# SmartLED1.net
KiCad netlist of a schematic drawn in Altium Designer
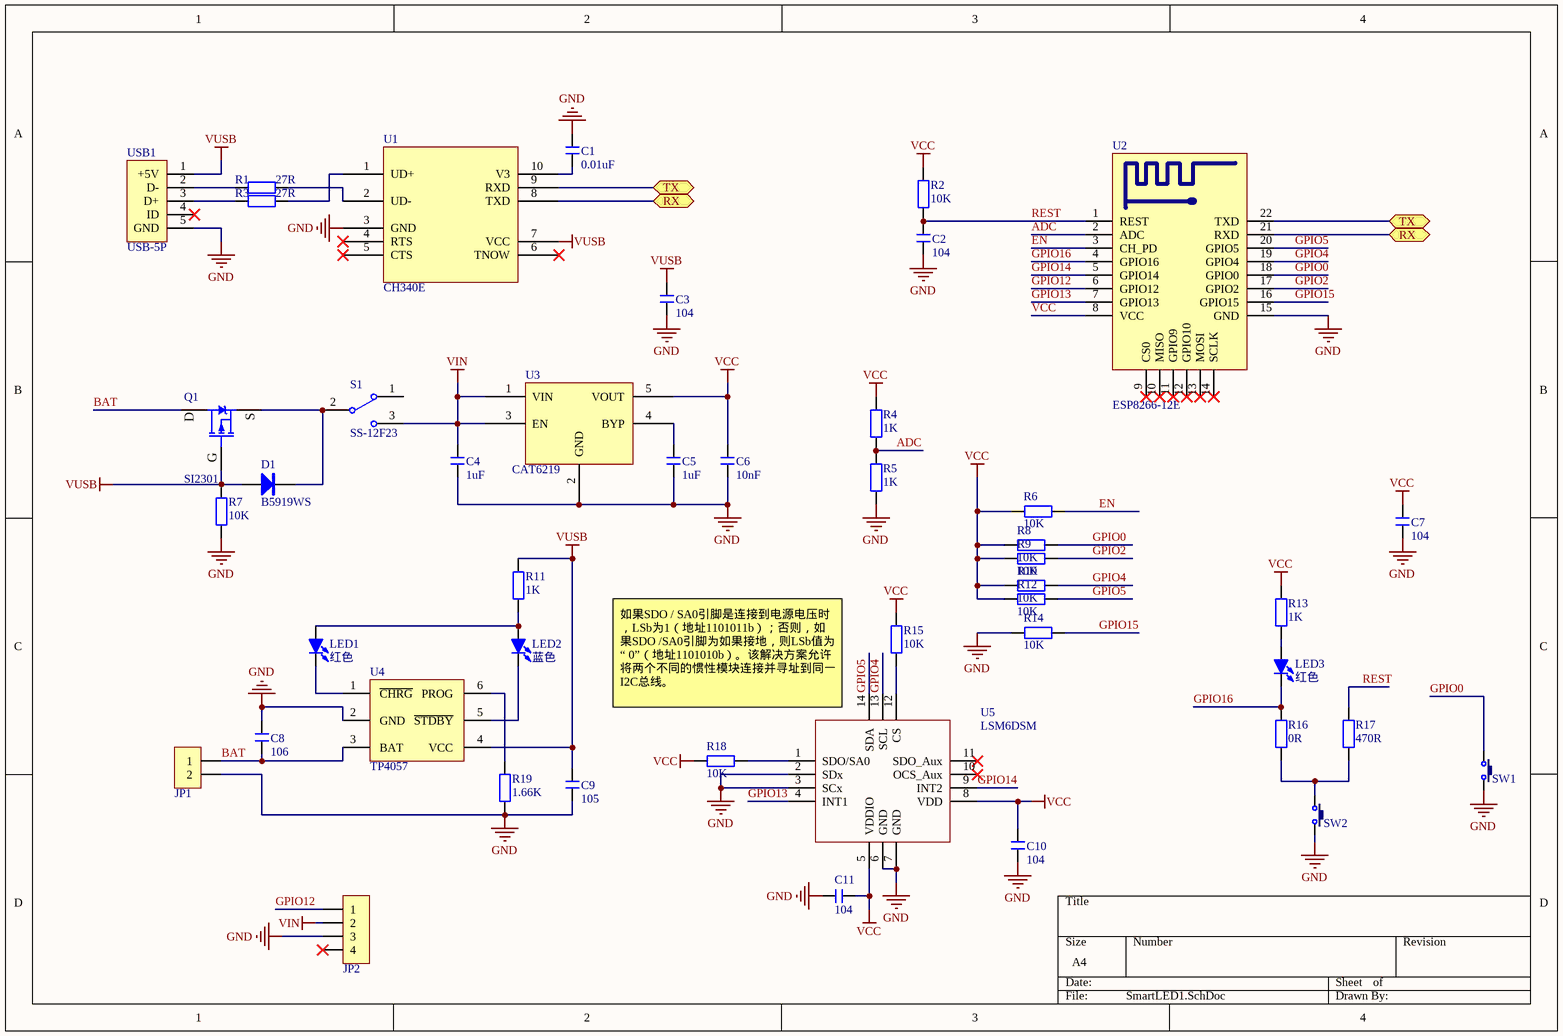
[diagram p0: SmartLED1.SchDoc]

(export (version "E")
  (design (tool "Eeschema 10.0.6"))
  (components
    (comp (ref "C1")
      (value "0.01uF")
      (footprint "C 0603_L")
      (description "无极性贴片电容")
      (fields (field (name "版权归属") "源创客"))
      (libsource (lib "3.1   - 电阻-电容-电感") (part "C"))
    )
    (comp (ref "C2")
      (value "104")
      (footprint "C 0603_L")
      (description "无极性贴片电容")
      (fields (field (name "版权归属") "源创客"))
      (libsource (lib "3.1   - 电阻-电容-电感") (part "C"))
    )
    (comp (ref "C3")
      (value "104")
      (footprint "C 0603_L")
      (description "无极性贴片电容")
      (fields (field (name "版权归属") "源创客"))
      (libsource (lib "3.1   - 电阻-电容-电感") (part "C"))
    )
    (comp (ref "C4")
      (value "1uF")
      (footprint "C 0603_L")
      (description "无极性贴片电容")
      (fields (field (name "版权归属") "源创客"))
      (libsource (lib "3.1   - 电阻-电容-电感") (part "C"))
    )
    (comp (ref "C5")
      (value "1uF")
      (footprint "C 0603_L")
      (description "无极性贴片电容")
      (fields (field (name "版权归属") "源创客"))
      (libsource (lib "3.1   - 电阻-电容-电感") (part "C"))
    )
    (comp (ref "C6")
      (value "10nF")
      (footprint "C 0603_L")
      (description "无极性贴片电容")
      (fields (field (name "版权归属") "源创客"))
      (libsource (lib "3.1   - 电阻-电容-电感") (part "C"))
    )
    (comp (ref "C7")
      (value "104")
      (footprint "C 0603_L")
      (description "无极性贴片电容")
      (fields (field (name "版权归属") "源创客"))
      (libsource (lib "3.1   - 电阻-电容-电感") (part "C"))
    )
    (comp (ref "C8")
      (value "106")
      (footprint "C 0603_L")
      (description "无极性贴片电容")
      (fields (field (name "版权归属") "源创客"))
      (libsource (lib "3.1   - 电阻-电容-电感") (part "C"))
    )
    (comp (ref "C9")
      (value "105")
      (footprint "C 0603_L")
      (description "无极性贴片电容")
      (fields (field (name "版权归属") "源创客"))
      (libsource (lib "3.1   - 电阻-电容-电感") (part "C"))
    )
    (comp (ref "C10")
      (value "104")
      (footprint "C 0603_L")
      (description "无极性贴片电容")
      (fields (field (name "版权归属") "源创客"))
      (libsource (lib "3.1   - 电阻-电容-电感") (part "C"))
    )
    (comp (ref "C11")
      (value "104")
      (footprint "C 0603_L")
      (description "无极性贴片电容")
      (fields (field (name "版权归属") "源创客"))
      (libsource (lib "3.1   - 电阻-电容-电感") (part "C"))
    )
    (comp (ref "D1")
      (value "B5919WS")
      (footprint "SOD-323")
      (description "肖特基二极管")
      (fields (field (name "版权归属") "源创客"))
      (libsource (lib "8.1   - 二极管-整流桥") (part "1N5819"))
    )
    (comp (ref "JP1")
      (value "HDR-1X2")
      (footprint "PH2.0-WS-2P")
      (description "2P接插件")
      (fields (field (name "版权归属") "源创客"))
      (libsource (lib "4.4   - 接插件-脚距2.0") (part "Header 2"))
    )
    (comp (ref "JP2")
      (value "HDR-1X4")
      (footprint "HDR2.54-M-LI-4P")
      (description "4P接插件")
      (fields (field (name "版权归属") "源创客"))
      (libsource (lib "4.5   - 接插件-脚距2.54") (part "Header 4"))
    )
    (comp (ref "LED1")
      (value "红色")
      (footprint "LED 0603G")
      (description "贴片LED")
      (fields (field (name "版权归属") "源创客"))
      (libsource (lib "9.1   - LED") (part "LED-SMD"))
    )
    (comp (ref "LED2")
      (value "蓝色")
      (footprint "LED 0603B")
      (description "贴片LED")
      (fields (field (name "版权归属") "源创客"))
      (libsource (lib "9.1   - LED") (part "LED-SMD"))
    )
    (comp (ref "LED3")
      (value "红色")
      (footprint "LED 0603Y")
      (description "贴片LED")
      (fields (field (name "版权归属") "源创客"))
      (libsource (lib "9.1   - LED") (part "LED-SMD"))
    )
    (comp (ref "Q1")
      (value "SI2301")
      (footprint "SOT23-3N")
      (description "P沟道场效应管")
      (fields (field (name "版权归属") "源创客"))
      (libsource (lib "6.1   - 场效应管-可控硅") (part "SI2301"))
    )
    (comp (ref "R1")
      (value "27R")
      (footprint "R 0603_L")
      (description "贴片电阻")
      (fields (field (name "版权归属") "源创客"))
      (libsource (lib "3.1   - 电阻-电容-电感") (part "R"))
    )
    (comp (ref "R2")
      (value "10K")
      (footprint "R 0603_L")
      (description "贴片电阻")
      (fields (field (name "版权归属") "源创客"))
      (libsource (lib "3.1   - 电阻-电容-电感") (part "R"))
    )
    (comp (ref "R3")
      (value "27R")
      (footprint "R 0603_L")
      (description "贴片电阻")
      (fields (field (name "版权归属") "源创客"))
      (libsource (lib "3.1   - 电阻-电容-电感") (part "R"))
    )
    (comp (ref "R4")
      (value "1K")
      (footprint "光敏电阻")
      (description "贴片电阻")
      (fields (field (name "版权归属") "源创客"))
      (libsource (lib "3.1   - 电阻-电容-电感") (part "R"))
    )
    (comp (ref "R5")
      (value "1K")
      (footprint "R 0603_L")
      (description "贴片电阻")
      (fields (field (name "版权归属") "源创客"))
      (libsource (lib "3.1   - 电阻-电容-电感") (part "R"))
    )
    (comp (ref "R6")
      (value "10K")
      (footprint "R 0603_L")
      (description "贴片电阻")
      (fields (field (name "版权归属") "源创客"))
      (libsource (lib "3.1   - 电阻-电容-电感") (part "R"))
    )
    (comp (ref "R7")
      (value "10K")
      (footprint "R 0603_L")
      (description "贴片电阻")
      (fields (field (name "版权归属") "源创客"))
      (libsource (lib "3.1   - 电阻-电容-电感") (part "R"))
    )
    (comp (ref "R8")
      (value "10K")
      (footprint "R 0603_L")
      (description "贴片电阻")
      (fields (field (name "版权归属") "源创客"))
      (libsource (lib "3.1   - 电阻-电容-电感") (part "R"))
    )
    (comp (ref "R9")
      (value "10K")
      (footprint "R 0603_L")
      (description "贴片电阻")
      (fields (field (name "版权归属") "源创客"))
      (libsource (lib "3.1   - 电阻-电容-电感") (part "R"))
    )
    (comp (ref "R10")
      (value "10K")
      (footprint "R 0603_L")
      (description "贴片电阻")
      (fields (field (name "版权归属") "源创客"))
      (libsource (lib "3.1   - 电阻-电容-电感") (part "R"))
    )
    (comp (ref "R11")
      (value "1K")
      (footprint "R 0603_L")
      (description "贴片电阻")
      (fields (field (name "版权归属") "源创客"))
      (libsource (lib "3.1   - 电阻-电容-电感") (part "R"))
    )
    (comp (ref "R12")
      (value "10K")
      (footprint "R 0603_L")
      (description "贴片电阻")
      (fields (field (name "版权归属") "源创客"))
      (libsource (lib "3.1   - 电阻-电容-电感") (part "R"))
    )
    (comp (ref "R13")
      (value "1K")
      (footprint "R 0603_L")
      (description "贴片电阻")
      (fields (field (name "版权归属") "源创客"))
      (libsource (lib "3.1   - 电阻-电容-电感") (part "R"))
    )
    (comp (ref "R14")
      (value "10K")
      (footprint "R 0603_L")
      (description "贴片电阻")
      (fields (field (name "版权归属") "源创客"))
      (libsource (lib "3.1   - 电阻-电容-电感") (part "R"))
    )
    (comp (ref "R15")
      (value "10K")
      (footprint "R 0603_L")
      (description "贴片电阻")
      (fields (field (name "版权归属") "源创客"))
      (libsource (lib "3.1   - 电阻-电容-电感") (part "R"))
    )
    (comp (ref "R16")
      (value "0R")
      (footprint "R 0603_L")
      (description "贴片电阻")
      (fields (field (name "版权归属") "源创客"))
      (libsource (lib "3.1   - 电阻-电容-电感") (part "R"))
    )
    (comp (ref "R17")
      (value "470R")
      (footprint "R 0603_L")
      (description "贴片电阻")
      (fields (field (name "版权归属") "源创客"))
      (libsource (lib "3.1   - 电阻-电容-电感") (part "R"))
    )
    (comp (ref "R18")
      (value "10K")
      (footprint "R 0603_L")
      (description "贴片电阻")
      (fields (field (name "版权归属") "源创客"))
      (libsource (lib "3.1   - 电阻-电容-电感") (part "R"))
    )
    (comp (ref "R19")
      (value "1.66K")
      (footprint "R 0603_L")
      (description "贴片电阻")
      (fields (field (name "版权归属") "源创客"))
      (libsource (lib "3.1   - 电阻-电容-电感") (part "R"))
    )
    (comp (ref "S1")
      (value "SS-12F23")
      (footprint "SK12D07")
      (description "1路波动开关")
      (fields (field (name "版权归属") "源创客"))
      (libsource (lib "5.1   - 按键-开关") (part "SSW-1P"))
    )
    (comp (ref "SW1")
      (value "3x6x5")
      (footprint "TSW 3*6*4.3-S-W")
      (description "3x6轻触开关")
      (fields (field (name "版权归属") "源创客"))
      (libsource (lib "5.1   - 按键-开关") (part "TSW 3x6"))
    )
    (comp (ref "SW2")
      (value "3x6x5")
      (footprint "TSW 3*6*4.3-S-W")
      (description "3x6轻触开关")
      (fields (field (name "版权归属") "源创客"))
      (libsource (lib "5.1   - 按键-开关") (part "TSW 3x6"))
    )
    (comp (ref "U1")
      (value "CH340E")
      (footprint "MSOP10_L")
      (libsource (lib "STM32F103RETX") (part "CH340E"))
    )
    (comp (ref "U2")
      (value "ESP8266-12E")
      (footprint "ESP_12E")
      (description "串口 WIFI模块，ESP-12E")
      (fields (field (name "版权归属") "源创客"))
      (libsource (lib "13.1 - 模块") (part "ESP8266-12E"))
    )
    (comp (ref "U3")
      (value "CAT6219")
      (footprint "SOT23-5N")
      (libsource (lib "STM32F103RETX") (part "CAT6219"))
    )
    (comp (ref "U4")
      (value "TP4057")
      (footprint "SOT23-6N")
      (libsource (lib "1.3   - 电源类芯片") (part "TP4057"))
    )
    (comp (ref "U5")
      (value "LSM6DSM")
      (footprint "LSM6DSM")
      (description "LSM6DSM 六轴传感器，牛皮")
      (libsource (lib "1.1   - IC芯片") (part "LSM6DSM"))
    )
    (comp (ref "USB1")
      (value "USB-5P")
      (footprint "USB-MICRO_B")
      (description "微型USB母座")
      (fields (field (name "版权归属") "源创客"))
      (libsource (lib "接口类") (part "USB-5P"))
    )
  )
  (nets
    (net (code "1") (name "/ADC") (class "Default")
      (node (ref "R4") (pin "1") (pinfunction "1_1") (pintype "passive"))
      (node (ref "R5") (pin "2") (pinfunction "2_2") (pintype "passive"))
      (node (ref "U2") (pin "2") (pinfunction "ADC_2") (pintype "passive"))
    )
    (net (code "2") (name "/BAT") (class "Default")
      (node (ref "C8") (pin "1") (pinfunction "1_1") (pintype "passive"))
      (node (ref "JP1") (pin "1") (pinfunction "1_1") (pintype "passive"))
      (node (ref "Q1") (pin "3") (pinfunction "D_3") (pintype "passive"))
      (node (ref "U4") (pin "3") (pinfunction "BAT_3") (pintype "passive"))
    )
    (net (code "3") (name "/EN") (class "Default")
      (node (ref "R6") (pin "1") (pinfunction "1_1") (pintype "passive"))
      (node (ref "U2") (pin "3") (pinfunction "CH_PD_3") (pintype "passive"))
    )
    (net (code "4") (name "/GPIO0") (class "Default")
      (node (ref "R8") (pin "1") (pinfunction "1_1") (pintype "passive"))
      (node (ref "SW1") (pin "1") (pinfunction "1_1") (pintype "passive"))
      (node (ref "U2") (pin "18") (pinfunction "GPIO0_18") (pintype "passive"))
    )
    (net (code "5") (name "/GPIO2") (class "Default")
      (node (ref "R9") (pin "1") (pinfunction "1_1") (pintype "passive"))
      (node (ref "U2") (pin "17") (pinfunction "GPIO2_17") (pintype "passive"))
    )
    (net (code "6") (name "/GPIO4") (class "Default")
      (node (ref "R10") (pin "1") (pinfunction "1_1") (pintype "passive"))
      (node (ref "U2") (pin "19") (pinfunction "GPIO4_19") (pintype "passive"))
      (node (ref "U5") (pin "13") (pinfunction "SCL_13") (pintype "passive"))
    )
    (net (code "7") (name "/GPIO5") (class "Default")
      (node (ref "R12") (pin "1") (pinfunction "1_1") (pintype "passive"))
      (node (ref "U2") (pin "20") (pinfunction "GPIO5_20") (pintype "passive"))
      (node (ref "U5") (pin "14") (pinfunction "SDA_14") (pintype "passive"))
    )
    (net (code "8") (name "/GPIO12") (class "Default")
      (node (ref "JP2") (pin "1") (pinfunction "1_1") (pintype "passive"))
      (node (ref "U2") (pin "6") (pinfunction "GPIO12_6") (pintype "passive"))
    )
    (net (code "9") (name "/GPIO13") (class "Default")
      (node (ref "U2") (pin "7") (pinfunction "GPIO13_7") (pintype "passive"))
      (node (ref "U5") (pin "4") (pinfunction "INT1_4") (pintype "passive"))
    )
    (net (code "10") (name "/GPIO14") (class "Default")
      (node (ref "U2") (pin "5") (pinfunction "GPIO14_5") (pintype "passive"))
      (node (ref "U5") (pin "9") (pinfunction "INT2_9") (pintype "passive"))
    )
    (net (code "11") (name "/GPIO15") (class "Default")
      (node (ref "R14") (pin "1") (pinfunction "1_1") (pintype "passive"))
      (node (ref "U2") (pin "16") (pinfunction "GPIO15_16") (pintype "passive"))
    )
    (net (code "12") (name "/GPIO16") (class "Default")
      (node (ref "LED3") (pin "2") (pinfunction "K_2") (pintype "passive"))
      (node (ref "R16") (pin "2") (pinfunction "2_2") (pintype "passive"))
      (node (ref "U2") (pin "4") (pinfunction "GPIO16_4") (pintype "passive"))
    )
    (net (code "13") (name "/REST") (class "Default")
      (node (ref "C2") (pin "2") (pinfunction "2_2") (pintype "passive"))
      (node (ref "R17") (pin "2") (pinfunction "2_2") (pintype "passive"))
      (node (ref "R2") (pin "1") (pinfunction "1_1") (pintype "passive"))
      (node (ref "U2") (pin "1") (pinfunction "REST_1") (pintype "passive"))
    )
    (net (code "14") (name "/RX") (class "Default")
      (node (ref "U1") (pin "8") (pinfunction "TXD_8") (pintype "passive"))
      (node (ref "U2") (pin "21") (pinfunction "RXD_21") (pintype "passive"))
    )
    (net (code "15") (name "/TX") (class "Default")
      (node (ref "U1") (pin "9") (pinfunction "RXD_9") (pintype "passive"))
      (node (ref "U2") (pin "22") (pinfunction "TXD_22") (pintype "passive"))
    )
    (net (code "16") (name "GND") (class "Default")
      (node (ref "C1") (pin "1") (pinfunction "1_1") (pintype "passive"))
      (node (ref "C10") (pin "1") (pinfunction "1_1") (pintype "passive"))
      (node (ref "C11") (pin "2") (pinfunction "2_2") (pintype "passive"))
      (node (ref "C2") (pin "1") (pinfunction "1_1") (pintype "passive"))
      (node (ref "C3") (pin "1") (pinfunction "1_1") (pintype "passive"))
      (node (ref "C4") (pin "1") (pinfunction "1_1") (pintype "passive"))
      (node (ref "C5") (pin "1") (pinfunction "1_1") (pintype "passive"))
      (node (ref "C6") (pin "1") (pinfunction "1_1") (pintype "passive"))
      (node (ref "C7") (pin "1") (pinfunction "1_1") (pintype "passive"))
      (node (ref "C8") (pin "2") (pinfunction "2_2") (pintype "passive"))
      (node (ref "C9") (pin "2") (pinfunction "2_2") (pintype "passive"))
      (node (ref "JP1") (pin "2") (pinfunction "2_2") (pintype "passive"))
      (node (ref "JP2") (pin "3") (pinfunction "3_3") (pintype "passive"))
      (node (ref "R14") (pin "2") (pinfunction "2_2") (pintype "passive"))
      (node (ref "R19") (pin "1") (pinfunction "1_1") (pintype "passive"))
      (node (ref "R5") (pin "1") (pinfunction "1_1") (pintype "passive"))
      (node (ref "R7") (pin "2") (pinfunction "2_2") (pintype "passive"))
      (node (ref "SW1") (pin "2") (pinfunction "2_2") (pintype "passive"))
      (node (ref "SW2") (pin "2") (pinfunction "2_2") (pintype "passive"))
      (node (ref "U1") (pin "3") (pinfunction "GND_3") (pintype "passive"))
      (node (ref "U2") (pin "15") (pinfunction "GND_15") (pintype "passive"))
      (node (ref "U3") (pin "2") (pinfunction "GND_2") (pintype "passive"))
      (node (ref "U4") (pin "2") (pinfunction "GND_2") (pintype "passive"))
      (node (ref "U5") (pin "2") (pinfunction "SDx_2") (pintype "passive"))
      (node (ref "U5") (pin "3") (pinfunction "SCx_3") (pintype "passive"))
      (node (ref "U5") (pin "6") (pinfunction "GND_6") (pintype "passive"))
      (node (ref "U5") (pin "7") (pinfunction "GND_7") (pintype "passive"))
      (node (ref "USB1") (pin "5") (pinfunction "GND_5") (pintype "passive"))
    )
    (net (code "17") (name "Net-(D1-K)") (class "Default")
      (node (ref "D1") (pin "2") (pinfunction "K_2") (pintype "passive"))
      (node (ref "Q1") (pin "2") (pinfunction "S_2") (pintype "passive"))
      (node (ref "S1") (pin "2") (pinfunction "2_2") (pintype "passive"))
    )
    (net (code "18") (name "Net-(LED1-A)") (class "Default")
      (node (ref "LED1") (pin "1") (pinfunction "A_1") (pintype "passive"))
      (node (ref "LED2") (pin "1") (pinfunction "A_1") (pintype "passive"))
      (node (ref "R11") (pin "2") (pinfunction "2_2") (pintype "passive"))
    )
    (net (code "19") (name "Net-(LED1-K)") (class "Default")
      (node (ref "LED1") (pin "2") (pinfunction "K_2") (pintype "passive"))
      (node (ref "U4") (pin "1") (pinfunction "~{CHRG}_1") (pintype "passive"))
    )
    (net (code "20") (name "Net-(LED2-K)") (class "Default")
      (node (ref "LED2") (pin "2") (pinfunction "K_2") (pintype "passive"))
      (node (ref "U4") (pin "5") (pinfunction "~{STDBY}_5") (pintype "passive"))
    )
    (net (code "21") (name "Net-(LED3-A)") (class "Default")
      (node (ref "LED3") (pin "1") (pinfunction "A_1") (pintype "passive"))
      (node (ref "R13") (pin "1") (pinfunction "1_1") (pintype "passive"))
    )
    (net (code "22") (name "Net-(R16-Pad1)") (class "Default")
      (node (ref "R16") (pin "1") (pinfunction "1_1") (pintype "passive"))
      (node (ref "R17") (pin "1") (pinfunction "1_1") (pintype "passive"))
      (node (ref "SW2") (pin "1") (pinfunction "1_1") (pintype "passive"))
    )
    (net (code "23") (name "Net-(U1-UD+)") (class "Default")
      (node (ref "R3") (pin "2") (pinfunction "2_2") (pintype "passive"))
      (node (ref "U1") (pin "1") (pinfunction "UD+_1") (pintype "passive"))
    )
    (net (code "24") (name "Net-(U1-UD-)") (class "Default")
      (node (ref "R1") (pin "2") (pinfunction "2_2") (pintype "passive"))
      (node (ref "U1") (pin "2") (pinfunction "UD-_2") (pintype "passive"))
    )
    (net (code "25") (name "Net-(U1-V3)") (class "Default")
      (node (ref "C1") (pin "2") (pinfunction "2_2") (pintype "passive"))
      (node (ref "U1") (pin "10") (pinfunction "V3_10") (pintype "passive"))
    )
    (net (code "26") (name "Net-(U3-BYP)") (class "Default")
      (node (ref "C5") (pin "2") (pinfunction "2_2") (pintype "passive"))
      (node (ref "U3") (pin "4") (pinfunction "BYP_4") (pintype "passive"))
    )
    (net (code "27") (name "Net-(U4-PROG)") (class "Default")
      (node (ref "R19") (pin "2") (pinfunction "2_2") (pintype "passive"))
      (node (ref "U4") (pin "6") (pinfunction "PROG_6") (pintype "passive"))
    )
    (net (code "28") (name "Net-(U5-CS)") (class "Default")
      (node (ref "R15") (pin "2") (pinfunction "2_2") (pintype "passive"))
      (node (ref "U5") (pin "12") (pinfunction "CS_12") (pintype "passive"))
    )
    (net (code "29") (name "Net-(U5-SDO{slash}SA0)") (class "Default")
      (node (ref "R18") (pin "2") (pinfunction "2_2") (pintype "passive"))
      (node (ref "U5") (pin "1") (pinfunction "SDO/SA0_1") (pintype "passive"))
    )
    (net (code "30") (name "Net-(USB1-D+)") (class "Default")
      (node (ref "R3") (pin "1") (pinfunction "1_1") (pintype "passive"))
      (node (ref "USB1") (pin "3") (pinfunction "D+_3") (pintype "passive"))
    )
    (net (code "31") (name "Net-(USB1-D-)") (class "Default")
      (node (ref "R1") (pin "1") (pinfunction "1_1") (pintype "passive"))
      (node (ref "USB1") (pin "2") (pinfunction "D-_2") (pintype "passive"))
    )
    (net (code "32") (name "VCC") (class "Default")
      (node (ref "C10") (pin "2") (pinfunction "2_2") (pintype "passive"))
      (node (ref "C11") (pin "1") (pinfunction "1_1") (pintype "passive"))
      (node (ref "C6") (pin "2") (pinfunction "2_2") (pintype "passive"))
      (node (ref "C7") (pin "2") (pinfunction "2_2") (pintype "passive"))
      (node (ref "R10") (pin "2") (pinfunction "2_2") (pintype "passive"))
      (node (ref "R12") (pin "2") (pinfunction "2_2") (pintype "passive"))
      (node (ref "R13") (pin "2") (pinfunction "2_2") (pintype "passive"))
      (node (ref "R15") (pin "1") (pinfunction "1_1") (pintype "passive"))
      (node (ref "R18") (pin "1") (pinfunction "1_1") (pintype "passive"))
      (node (ref "R2") (pin "2") (pinfunction "2_2") (pintype "passive"))
      (node (ref "R4") (pin "2") (pinfunction "2_2") (pintype "passive"))
      (node (ref "R6") (pin "2") (pinfunction "2_2") (pintype "passive"))
      (node (ref "R8") (pin "2") (pinfunction "2_2") (pintype "passive"))
      (node (ref "R9") (pin "2") (pinfunction "2_2") (pintype "passive"))
      (node (ref "U2") (pin "8") (pinfunction "VCC_8") (pintype "passive"))
      (node (ref "U3") (pin "5") (pinfunction "VOUT_5") (pintype "passive"))
      (node (ref "U5") (pin "5") (pinfunction "VDDIO_5") (pintype "passive"))
      (node (ref "U5") (pin "8") (pinfunction "VDD_8") (pintype "passive"))
    )
    (net (code "33") (name "VIN") (class "Default")
      (node (ref "C4") (pin "2") (pinfunction "2_2") (pintype "passive"))
      (node (ref "JP2") (pin "2") (pinfunction "2_2") (pintype "passive"))
      (node (ref "S1") (pin "3") (pinfunction "3_3") (pintype "passive"))
      (node (ref "U3") (pin "1") (pinfunction "VIN_1") (pintype "passive"))
      (node (ref "U3") (pin "3") (pinfunction "EN_3") (pintype "passive"))
    )
    (net (code "34") (name "VUSB") (class "Default")
      (node (ref "C3") (pin "2") (pinfunction "2_2") (pintype "passive"))
      (node (ref "C9") (pin "1") (pinfunction "1_1") (pintype "passive"))
      (node (ref "D1") (pin "1") (pinfunction "A_1") (pintype "passive"))
      (node (ref "Q1") (pin "1") (pinfunction "G_1") (pintype "passive"))
      (node (ref "R11") (pin "1") (pinfunction "1_1") (pintype "passive"))
      (node (ref "R7") (pin "1") (pinfunction "1_1") (pintype "passive"))
      (node (ref "U1") (pin "7") (pinfunction "VCC_7") (pintype "passive"))
      (node (ref "U4") (pin "4") (pinfunction "VCC_4") (pintype "passive"))
      (node (ref "USB1") (pin "1") (pinfunction "+5V_1") (pintype "passive"))
    )
    (net (code "35") (name "unconnected-(JP2-Pad4)") (class "Default")
      (node (ref "JP2") (pin "4") (pinfunction "4_4") (pintype "passive+no_connect"))
    )
    (net (code "36") (name "unconnected-(S1-Pad1)") (class "Default")
      (node (ref "S1") (pin "1") (pinfunction "1_1") (pintype "passive"))
    )
    (net (code "37") (name "unconnected-(U1-CTS-Pad5)") (class "Default")
      (node (ref "U1") (pin "5") (pinfunction "CTS_5") (pintype "passive+no_connect"))
    )
    (net (code "38") (name "unconnected-(U1-RTS-Pad4)") (class "Default")
      (node (ref "U1") (pin "4") (pinfunction "RTS_4") (pintype "passive+no_connect"))
    )
    (net (code "39") (name "unconnected-(U1-TNOW-Pad6)") (class "Default")
      (node (ref "U1") (pin "6") (pinfunction "TNOW_6") (pintype "passive+no_connect"))
    )
    (net (code "40") (name "unconnected-(U2-CS0-Pad9)") (class "Default")
      (node (ref "U2") (pin "9") (pinfunction "CS0_9") (pintype "passive+no_connect"))
    )
    (net (code "41") (name "unconnected-(U2-GPIO9-Pad11)") (class "Default")
      (node (ref "U2") (pin "11") (pinfunction "GPIO9_11") (pintype "passive+no_connect"))
    )
    (net (code "42") (name "unconnected-(U2-GPIO10-Pad12)") (class "Default")
      (node (ref "U2") (pin "12") (pinfunction "GPIO10_12") (pintype "passive+no_connect"))
    )
    (net (code "43") (name "unconnected-(U2-MISO-Pad10)") (class "Default")
      (node (ref "U2") (pin "10") (pinfunction "MISO_10") (pintype "passive+no_connect"))
    )
    (net (code "44") (name "unconnected-(U2-MOSI-Pad13)") (class "Default")
      (node (ref "U2") (pin "13") (pinfunction "MOSI_13") (pintype "passive+no_connect"))
    )
    (net (code "45") (name "unconnected-(U2-SCLK-Pad14)") (class "Default")
      (node (ref "U2") (pin "14") (pinfunction "SCLK_14") (pintype "passive+no_connect"))
    )
    (net (code "46") (name "unconnected-(U5-OCS_Aux-Pad10)") (class "Default")
      (node (ref "U5") (pin "10") (pinfunction "OCS_Aux_10") (pintype "passive+no_connect"))
    )
    (net (code "47") (name "unconnected-(U5-SDO_Aux-Pad11)") (class "Default")
      (node (ref "U5") (pin "11") (pinfunction "SDO_Aux_11") (pintype "passive+no_connect"))
    )
    (net (code "48") (name "unconnected-(USB1-ID-Pad4)") (class "Default")
      (node (ref "USB1") (pin "4") (pinfunction "ID_4") (pintype "passive+no_connect"))
    )
  )
)
